# Pi-puck_ToF.net
KiCad netlist of a schematic drawn in EAGLE
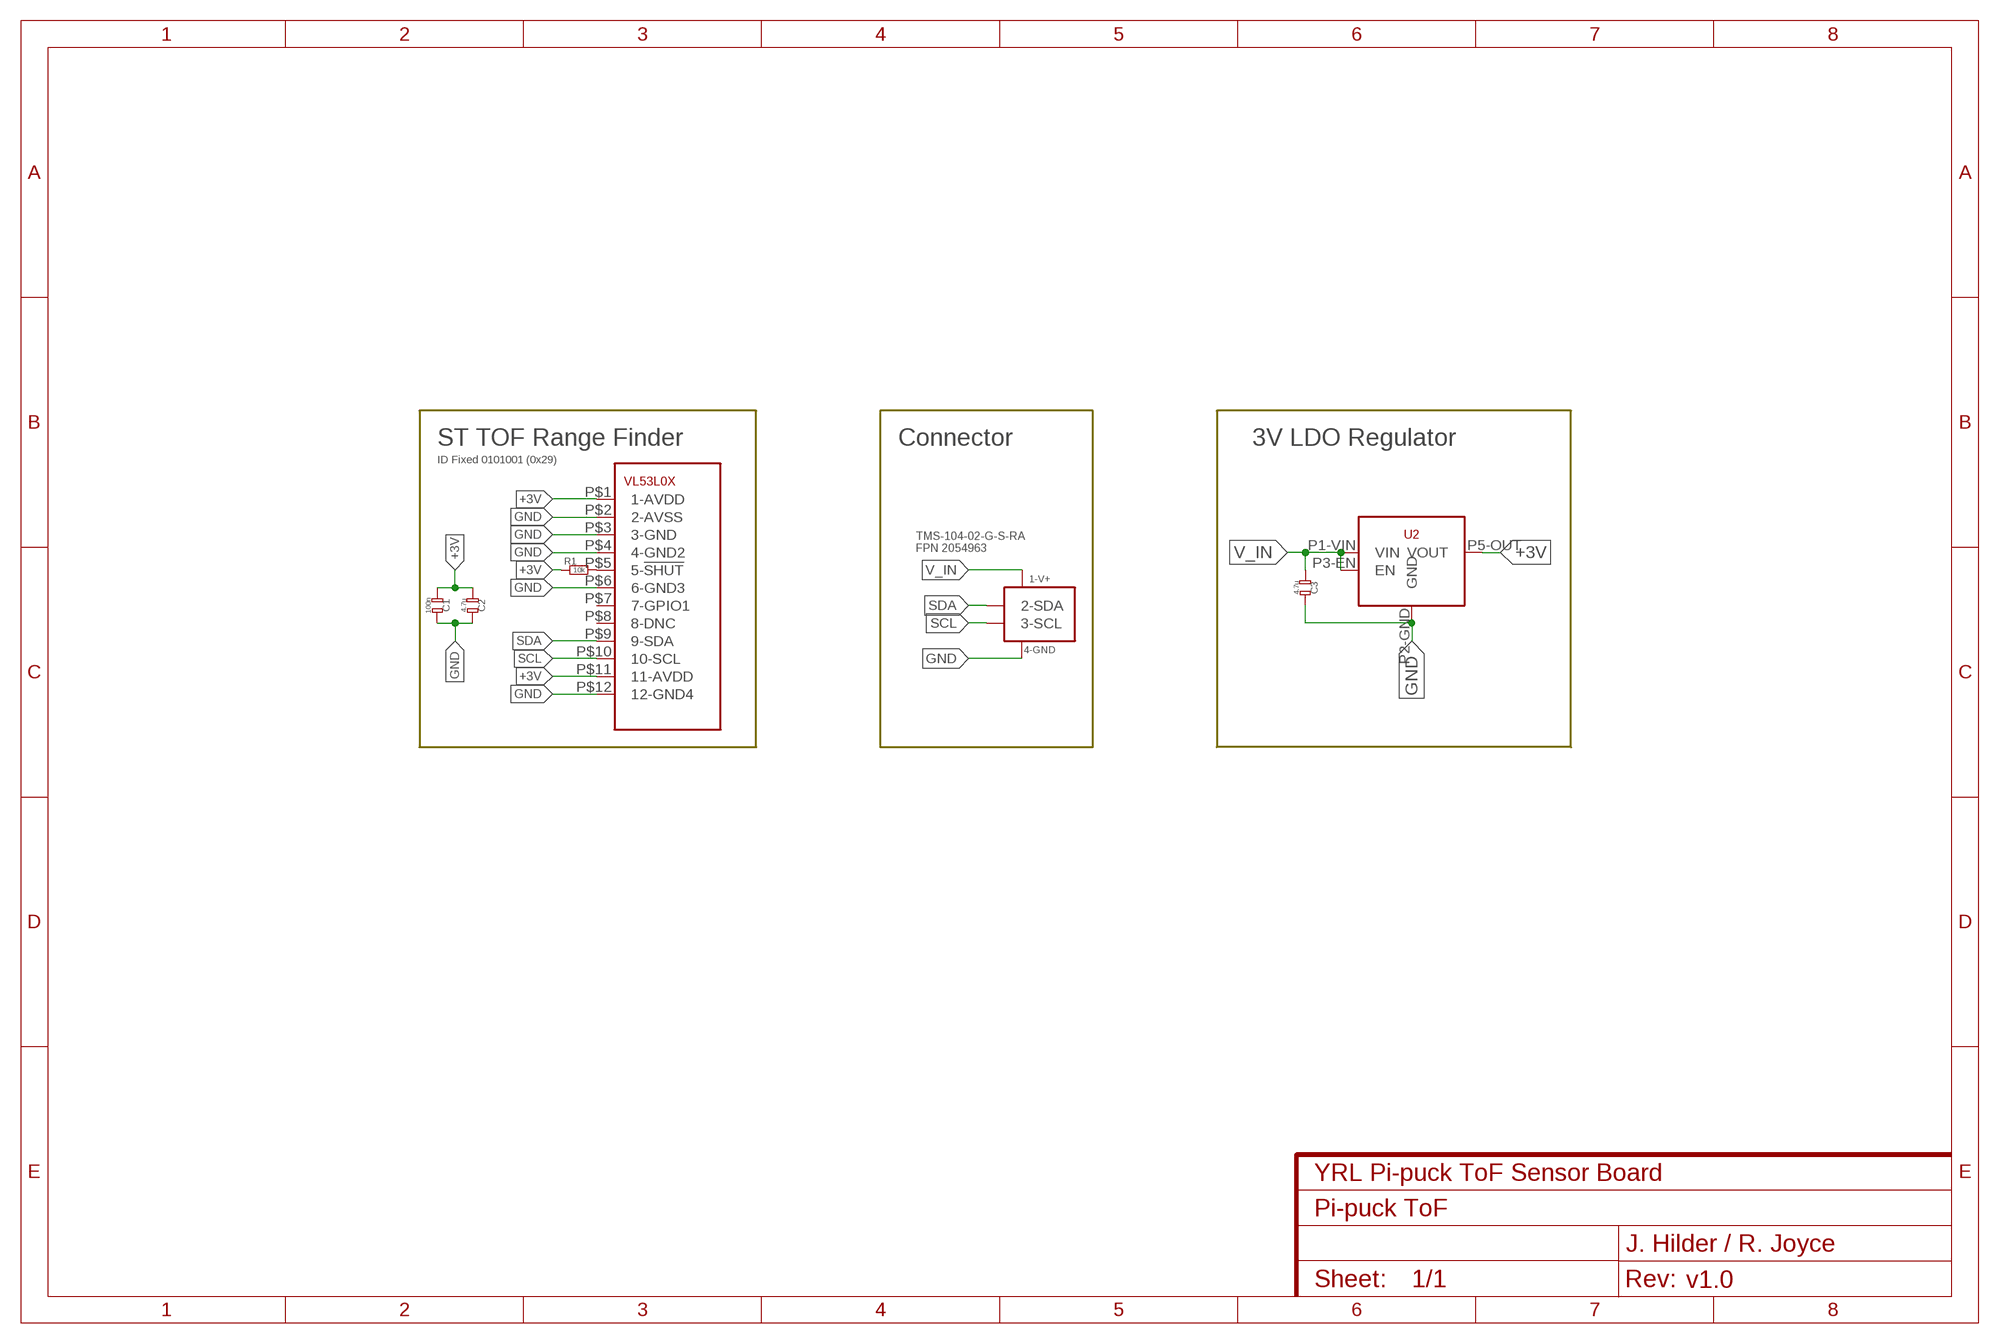
[diagram p0: schematic, sheet 1]

(export (version "E")
  (design (tool "Eeschema 10.0.6"))
  (components
    (comp (ref "C1")
      (value "100n")
      (footprint "eagle-import:0603-RESISTOR")
      (libsource (lib "eagle-import") (part "CAPACITOR-0603"))
    )
    (comp (ref "C2")
      (value "4.7u")
      (footprint "eagle-import:0603-RESISTOR")
      (libsource (lib "eagle-import") (part "CAPACITOR-0603"))
    )
    (comp (ref "C3")
      (value "4.7u")
      (footprint "eagle-import:0603-RESISTOR")
      (libsource (lib "eagle-import") (part "CAPACITOR-0603"))
    )
    (comp (ref "R1")
      (value "10k")
      (footprint "eagle-import:0603-RESISTOR")
      (libsource (lib "eagle-import") (part "RESISTOR-0603"))
    )
    (comp (ref "SC1")
      (value "4-PIN-SENSOR-2054963-REVERSED")
      (footprint "eagle-import:4-PIN-0.05_-PITCH-THROUGH-HOLE-RA-SENSOR-REVERSED")
      (libsource (lib "eagle-import") (part "4-PIN-SENSOR-2054963-REVERSED"))
    )
    (comp (ref "U1")
      (value "ST-VL53L0X")
      (footprint "eagle-import:VL53L0X")
      (libsource (lib "eagle-import") (part "ST-VL53L0X"))
    )
    (comp (ref "U2")
      (value "2851575-LIC5365-LDO-3V-SC-70-5")
      (footprint "eagle-import:MIC5365-3.0YC5-TR-SC70-5-LDO-VREG")
      (libsource (lib "eagle-import") (part "2851575-LIC5365-LDO-3V-SC-70-5"))
    )
  )
  (nets
    (net (code "1") (name "+3V") (class "Default")
      (node (ref "C1") (pin "1") (pinfunction "SD1_1") (pintype "passive"))
      (node (ref "C2") (pin "1") (pinfunction "SD1_1") (pintype "passive"))
      (node (ref "R1") (pin "1") (pinfunction "SD1_1") (pintype "passive"))
      (node (ref "U1") (pin "P$1") (pinfunction "1-AVDD_P$1") (pintype "bidirectional"))
      (node (ref "U1") (pin "P$11") (pinfunction "11-AVDD_P$11") (pintype "bidirectional"))
      (node (ref "U2") (pin "P5-OUT") (pinfunction "VOUT_P5-OUT") (pintype "bidirectional"))
    )
    (net (code "2") (name "GND") (class "Default")
      (node (ref "C1") (pin "2") (pinfunction "SD2_2") (pintype "passive"))
      (node (ref "C2") (pin "2") (pinfunction "SD2_2") (pintype "passive"))
      (node (ref "C3") (pin "2") (pinfunction "SD2_2") (pintype "passive"))
      (node (ref "SC1") (pin "1-GND") (pinfunction "4-GND_1-GND") (pintype "bidirectional"))
      (node (ref "U1") (pin "P$12") (pinfunction "12-GND4_P$12") (pintype "bidirectional"))
      (node (ref "U1") (pin "P$2") (pinfunction "2-AVSS_P$2") (pintype "bidirectional"))
      (node (ref "U1") (pin "P$3") (pinfunction "3-GND_P$3") (pintype "bidirectional"))
      (node (ref "U1") (pin "P$4") (pinfunction "4-GND2_P$4") (pintype "bidirectional"))
      (node (ref "U1") (pin "P$6") (pinfunction "6-GND3_P$6") (pintype "bidirectional"))
      (node (ref "U2") (pin "P2-GND") (pinfunction "GND_P2-GND") (pintype "bidirectional"))
    )
    (net (code "3") (name "Net-(R1-SD2)") (class "Default")
      (node (ref "R1") (pin "2") (pinfunction "SD2_2") (pintype "passive"))
      (node (ref "U1") (pin "P$5") (pinfunction "5-~{SHUT}_P$5") (pintype "bidirectional"))
    )
    (net (code "4") (name "SCL") (class "Default")
      (node (ref "SC1") (pin "2-SCL") (pinfunction "3-SCL_2-SCL") (pintype "bidirectional"))
      (node (ref "U1") (pin "P$10") (pinfunction "10-SCL_P$10") (pintype "bidirectional"))
    )
    (net (code "5") (name "SDA") (class "Default")
      (node (ref "SC1") (pin "3-SDA") (pinfunction "2-SDA_3-SDA") (pintype "bidirectional"))
      (node (ref "U1") (pin "P$9") (pinfunction "9-SDA_P$9") (pintype "bidirectional"))
    )
    (net (code "6") (name "V_IN") (class "Default")
      (node (ref "C3") (pin "1") (pinfunction "SD1_1") (pintype "passive"))
      (node (ref "SC1") (pin "4-V+") (pinfunction "1-V+_4-V+") (pintype "bidirectional"))
      (node (ref "U2") (pin "P1-VIN") (pinfunction "VIN_P1-VIN") (pintype "bidirectional"))
      (node (ref "U2") (pin "P3-EN") (pinfunction "EN_P3-EN") (pintype "bidirectional"))
    )
    (net (code "7") (name "unconnected-(U1-7-GPIO1-PadP$7)") (class "Default")
      (node (ref "U1") (pin "P$7") (pinfunction "7-GPIO1_P$7") (pintype "bidirectional"))
    )
    (net (code "8") (name "unconnected-(U1-8-DNC-PadP$8)") (class "Default")
      (node (ref "U1") (pin "P$8") (pinfunction "8-DNC_P$8") (pintype "no_connect"))
    )
  )
)
